# Supercap.net
KiCad netlist of a schematic drawn in EAGLE
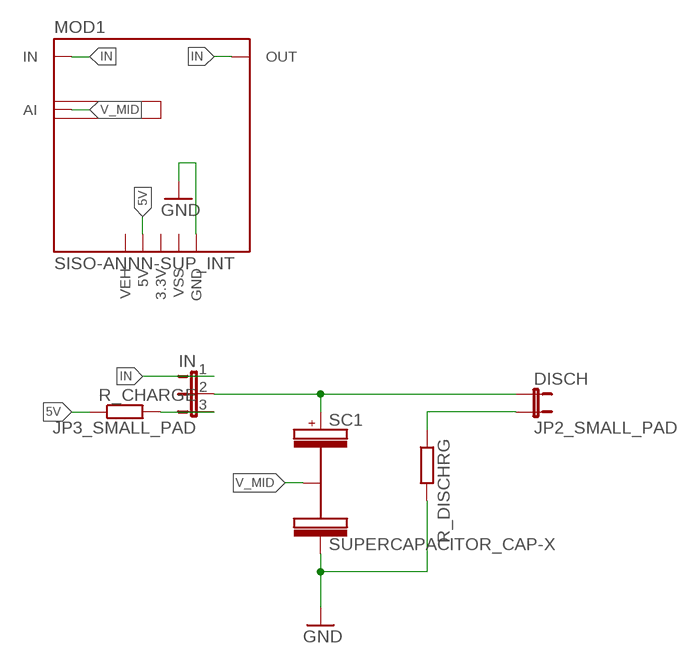
[diagram p0: schematic, sheet 1]

(export (version "E")
  (design (tool "Eeschema 10.0.6"))
  (components
    (comp (ref "DISCH")
      (value "JP2_SMALL_PAD")
      (footprint "eagle-import:JP2_SMALL_PAD")
      (libsource (lib "eagle-import") (part "JP2_SMALL_PAD"))
    )
    (comp (ref "IN")
      (value "JP3_SMALL_PAD")
      (footprint "eagle-import:JP3_SMALL_PAD")
      (libsource (lib "eagle-import") (part "JP3_SMALL_PAD"))
    )
    (comp (ref "MOD1")
      (value "SISO-ANNN-SUP_INT")
      (footprint "eagle-import:SISO-ANNN-SUP")
      (libsource (lib "eagle-import") (part "SISO-ANNN-SUP_INT"))
    )
    (comp (ref "R_CHARGE")
      (value "R_THROUGH-HOLE")
      (footprint "eagle-import:R_THROUGH-HOLE")
      (libsource (lib "eagle-import") (part "R_THROUGH-HOLE"))
    )
    (comp (ref "R_DISCHRG")
      (value "R_THROUGH-HOLE")
      (footprint "eagle-import:R_THROUGH-HOLE")
      (libsource (lib "eagle-import") (part "R_THROUGH-HOLE"))
    )
    (comp (ref "SC1")
      (value "SUPERCAPACITOR_CAP-X")
      (footprint "eagle-import:SUPERCAPACITOR_CAP-X")
      (libsource (lib "eagle-import") (part "SUPERCAPACITOR_CAP-X"))
    )
  )
  (nets
    (net (code "1") (name "/3.3V") (class "Default")
      (node (ref "MOD1") (pin "3.3V") (pinfunction "3.3V_3.3V") (pintype "power_in"))
    )
    (net (code "2") (name "/VEH") (class "Default")
      (node (ref "MOD1") (pin "VEH") (pinfunction "VEH_VEH") (pintype "power_in"))
    )
    (net (code "3") (name "/VSS") (class "Default")
      (node (ref "MOD1") (pin "VSS") (pinfunction "VSS_VSS") (pintype "power_in"))
    )
    (net (code "4") (name "5V") (class "Default")
      (node (ref "MOD1") (pin "5V") (pinfunction "5V_5V") (pintype "power_in"))
      (node (ref "R_CHARGE") (pin "1") (pinfunction "1_1") (pintype "passive"))
    )
    (net (code "5") (name "GND") (class "Default")
      (node (ref "MOD1") (pin "GND1") (pinfunction "GND_GND1") (pintype "power_in"))
      (node (ref "MOD1") (pin "GND2") (pinfunction "GND_GND2") (pintype "power_in"))
      (node (ref "MOD1") (pin "GND3") (pinfunction "GND_GND3") (pintype "power_in"))
      (node (ref "MOD1") (pin "GND4") (pinfunction "GND_GND4") (pintype "power_in"))
      (node (ref "R_DISCHRG") (pin "2") (pinfunction "2_2") (pintype "passive"))
      (node (ref "SC1") (pin "-1") (pinfunction "-1_-1") (pintype "passive"))
    )
    (net (code "6") (name "IN") (class "Default")
      (node (ref "IN") (pin "1") (pinfunction "1_1") (pintype "passive"))
      (node (ref "MOD1") (pin "IN1") (pinfunction "IN_IN1") (pintype "output"))
      (node (ref "MOD1") (pin "IN2") (pinfunction "IN_IN2") (pintype "output"))
      (node (ref "MOD1") (pin "IN3") (pinfunction "IN_IN3") (pintype "output"))
      (node (ref "MOD1") (pin "IN4") (pinfunction "IN_IN4") (pintype "output"))
      (node (ref "MOD1") (pin "OUT1") (pinfunction "OUT_OUT1") (pintype "input"))
      (node (ref "MOD1") (pin "OUT2") (pinfunction "OUT_OUT2") (pintype "input"))
      (node (ref "MOD1") (pin "OUT3") (pinfunction "OUT_OUT3") (pintype "input"))
      (node (ref "MOD1") (pin "OUT4") (pinfunction "OUT_OUT4") (pintype "input"))
    )
    (net (code "7") (name "Net-(DISCH-Pad1)") (class "Default")
      (node (ref "DISCH") (pin "1") (pinfunction "1_1") (pintype "passive"))
      (node (ref "IN") (pin "2") (pinfunction "2_2") (pintype "passive"))
      (node (ref "SC1") (pin "+") (pinfunction "+_+") (pintype "passive"))
    )
    (net (code "8") (name "Net-(DISCH-Pad2)") (class "Default")
      (node (ref "DISCH") (pin "2") (pinfunction "2_2") (pintype "passive"))
      (node (ref "R_DISCHRG") (pin "1") (pinfunction "1_1") (pintype "passive"))
    )
    (net (code "9") (name "Net-(IN-Pad3)") (class "Default")
      (node (ref "IN") (pin "3") (pinfunction "3_3") (pintype "passive"))
      (node (ref "R_CHARGE") (pin "2") (pinfunction "2_2") (pintype "passive"))
    )
    (net (code "10") (name "V_MID") (class "Default")
      (node (ref "MOD1") (pin "AI") (pinfunction "AI_AI") (pintype "output"))
      (node (ref "SC1") (pin "V_MID") (pinfunction "V_MID_V_MID") (pintype "bidirectional"))
    )
  )
)
